# Sheet1.net
KiCad netlist of a schematic drawn in Altium Designer
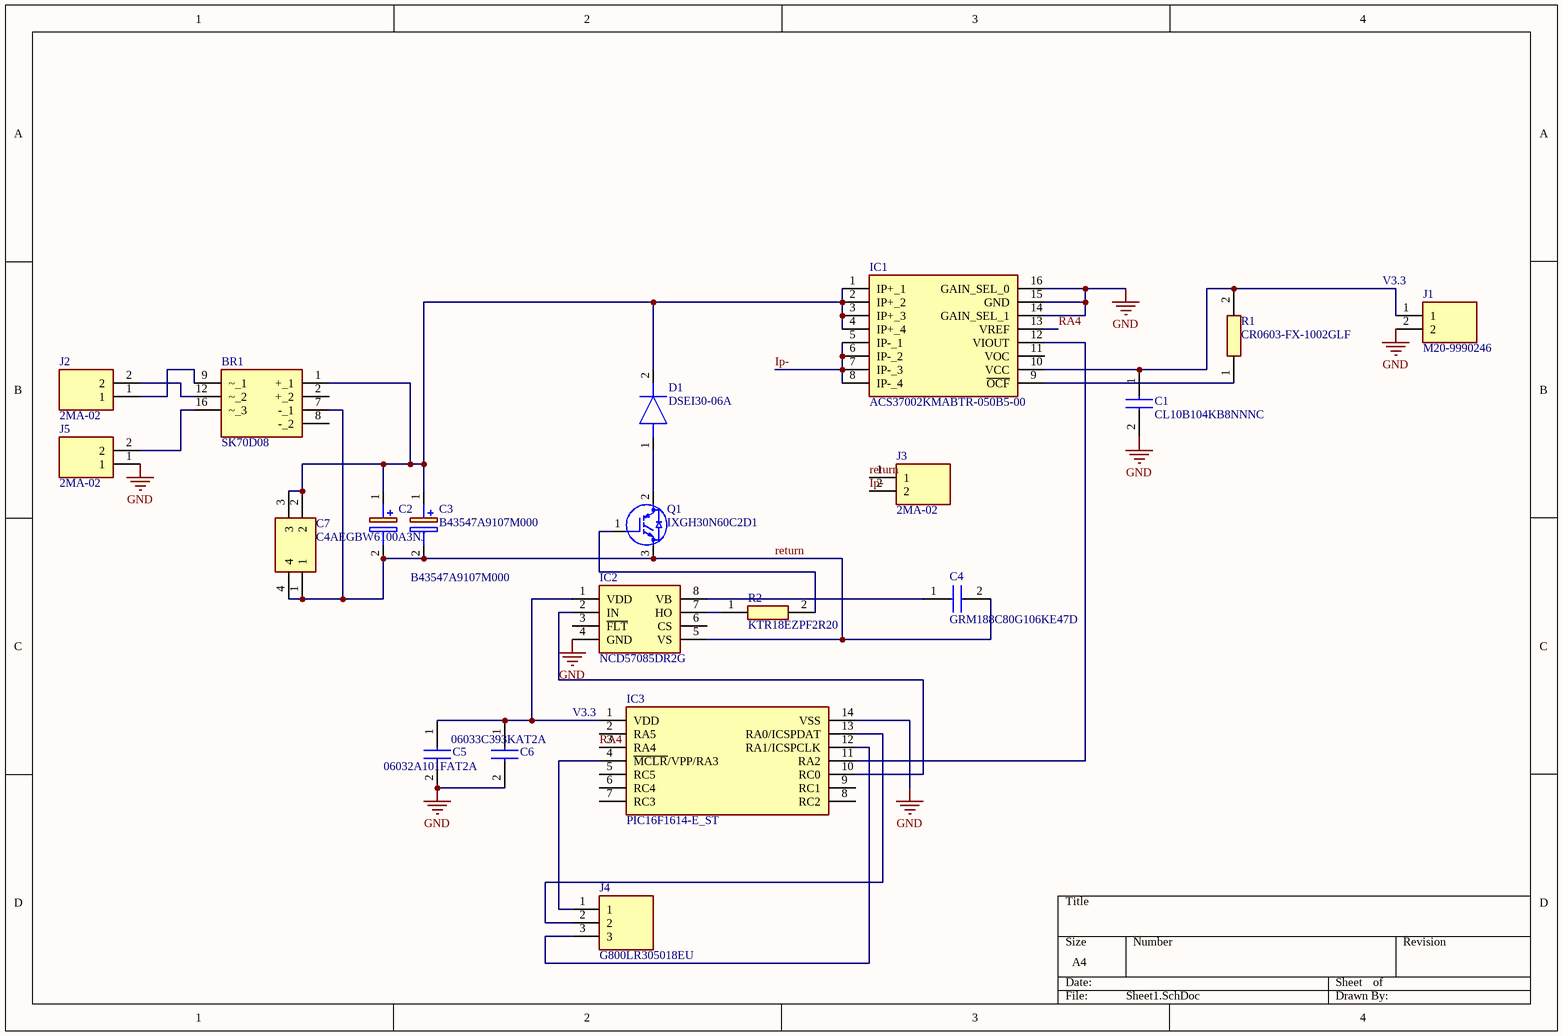
[diagram p0: Sheet1.SchDoc]

(export (version "E")
  (design (tool "Eeschema 10.0.6"))
  (components
    (comp (ref "BR1")
      (value "SK70D08")
      (footprint "SamacSys:SK70D08")
      (description "Bridge Rectifier")
      (libsource (lib "*") (part "SK70D08"))
    )
    (comp (ref "C1")
      (value "CL10B104KB8NNNC")
      (footprint "SamacSys:CAPC1608X90N")
      (description "Capacitor")
      (fields (field (name "MOUSER PART NUMBER") "187-CL10B104KB8NNNC"))
      (libsource (lib "*") (part "CL10B104KB8NNNC"))
    )
    (comp (ref "C2")
      (value "B43547A9107M000")
      (footprint "SamacSys:CAPPRD1000W190D2550H2700")
      (description "Capacitor Polarised")
      (fields (field (name "MOUSER PART NUMBER") "871-B43547A9107M000"))
      (libsource (lib "*") (part "B43547A9107M000"))
    )
    (comp (ref "C3")
      (value "B43547A9107M000")
      (footprint "SamacSys:CAPPRD1000W190D2550H2700")
      (description "Capacitor Polarised")
      (fields (field (name "MOUSER PART NUMBER") "871-B43547A9107M000"))
      (libsource (lib "*") (part "B43547A9107M000"))
    )
    (comp (ref "C4")
      (value "GRM188C80G106KE47D")
      (footprint "SamacSys:CAPC1608X90N")
      (description "Capacitor")
      (fields (field (name "MOUSER PART NUMBER") "81-GRM188C80G106KE7D"))
      (libsource (lib "*") (part "GRM188C80G106KE47D"))
    )
    (comp (ref "C5")
      (value "06032A101FAT2A")
      (footprint "SamacSys:CAPC1608X90N")
      (description "Capacitor")
      (fields (field (name "MOUSER PART NUMBER") "581-06032A101FAT2A"))
      (libsource (lib "*") (part "06032A101FAT2A"))
    )
    (comp (ref "C6")
      (value "06033C393KAT2A")
      (footprint "SamacSys:CAPC1608X90N")
      (description "Capacitor")
      (fields (field (name "MOUSER PART NUMBER") "581-06033C393K"))
      (libsource (lib "*") (part "06033C393KAT2A"))
    )
    (comp (ref "C7")
      (value "C4AEGBW6100A3NJ")
      (footprint "SamacSys:C4AEGBW6100A3NJ")
      (description "Capacitor")
      (libsource (lib "*") (part "C4AEGBW6100A3NJ"))
    )
    (comp (ref "D1")
      (value "DSEI30-06A")
      (footprint "SamacSys:TO1092P530X1586X2594-2P")
      (description "Diode")
      (fields (field (name "MOUSER PART NUMBER") "747-DSEI30-06A"))
      (libsource (lib "*") (part "DSEI30-06A"))
    )
    (comp (ref "IC1")
      (value "ACS37002KMABTR-050B5-00")
      (footprint "SamacSys:SOIC127P1030X265-16N")
      (description "Integrated Circuit")
      (libsource (lib "*") (part "ACS37002KMABTR-050B5-00"))
    )
    (comp (ref "IC2")
      (value "NCD57085DR2G")
      (footprint "SamacSys:SOIC127P600X175-8N")
      (description "Integrated Circuit")
      (fields (field (name "MOUSER PART NUMBER") "863-NCD57085DR2G"))
      (libsource (lib "*") (part "NCD57085DR2G"))
    )
    (comp (ref "IC3")
      (value "PIC16F1614-E_ST")
      (footprint "SamacSys:SOP65P640X120-14N")
      (description "Integrated Circuit")
      (fields
        (field (name "MANUFACTURER_PART_NUMBER") "PIC16F1614-E/ST")
        (field (name "MOUSER PART NUMBER") "579-PIC16F1614-E/ST")
      )
      (libsource (lib "*") (part "PIC16F1614-E_ST"))
    )
    (comp (ref "J1")
      (value "M20-9990246")
      (footprint "SamacSys:HDRV2W66P0X254_1X2_508X254X874P")
      (description "Connector")
      (fields (field (name "MOUSER PART NUMBER") "855-M20-9990246"))
      (libsource (lib "*") (part "M20-9990246"))
    )
    (comp (ref "J2")
      (value "2MA-02")
      (footprint "SamacSys:2MA02")
      (description "Connector")
      (fields (field (name "MOUSER PART NUMBER") "571-15460742"))
      (libsource (lib "*") (part "2MA-02"))
    )
    (comp (ref "J3")
      (value "2MA-02")
      (footprint "SamacSys:2MA02")
      (description "Connector")
      (fields (field (name "MOUSER PART NUMBER") "571-15460742"))
      (libsource (lib "") (part "2MA-02_1"))
    )
    (comp (ref "J4")
      (value "G800LR305018EU")
      (footprint "SamacSys:HDRV3W64P0X254_1X3_762X250X1082P")
      (description "Connector")
      (fields (field (name "MOUSER PART NUMBER") "523-G800LR305018EU"))
      (libsource (lib "*") (part "G800LR305018EU"))
    )
    (comp (ref "J5")
      (value "2MA-02")
      (footprint "SamacSys:2MA02")
      (description "Connector")
      (fields (field (name "MOUSER PART NUMBER") "571-15460742"))
      (libsource (lib "*") (part "2MA-02"))
    )
    (comp (ref "Q1")
      (value "IXGH30N60C2D1")
      (footprint "SamacSys:IXGH30N60C2D1")
      (description "Transistor IGBT")
      (libsource (lib "*") (part "IXGH30N60C2D1"))
    )
    (comp (ref "R1")
      (value "CR0603-FX-1002GLF")
      (footprint "SamacSys:RESC1608X55N")
      (description "Resistor")
      (fields (field (name "MOUSER PART NUMBER") "652-CR0603FX-1002GLF"))
      (libsource (lib "*") (part "CR0603-FX-1002GLF"))
    )
    (comp (ref "R2")
      (value "KTR18EZPF2R20")
      (footprint "SamacSys:RESC3216X65N")
      (description "Resistor")
      (fields (field (name "MOUSER PART NUMBER") "755-KTR18EZPF2R20"))
      (libsource (lib "*") (part "KTR18EZPF2R20"))
    )
  )
  (nets
    (net (code "1") (name "/Ip-") (class "Default")
      (node (ref "IC1") (pin "5") (pinfunction "IP-_1_5") (pintype "passive"))
      (node (ref "IC1") (pin "6") (pinfunction "IP-_2_6") (pintype "passive"))
      (node (ref "IC1") (pin "7") (pinfunction "IP-_3_7") (pintype "passive"))
      (node (ref "IC1") (pin "8") (pinfunction "IP-_4_8") (pintype "passive"))
      (node (ref "J3") (pin "2") (pinfunction "2_2") (pintype "passive"))
    )
    (net (code "2") (name "/RA4") (class "Default")
      (node (ref "IC1") (pin "13") (pinfunction "VREF_13") (pintype "passive"))
      (node (ref "IC3") (pin "3") (pinfunction "RA4_3") (pintype "passive"))
    )
    (net (code "3") (name "/return") (class "Default")
      (node (ref "BR1") (pin "7") (pinfunction "-_1_7") (pintype "passive"))
      (node (ref "C2") (pin "2") (pinfunction "-_2") (pintype "passive"))
      (node (ref "C3") (pin "2") (pinfunction "-_2") (pintype "passive"))
      (node (ref "C4") (pin "2") (pinfunction "2_2") (pintype "passive"))
      (node (ref "C7") (pin "1") (pinfunction "1_1") (pintype "passive"))
      (node (ref "C7") (pin "4") (pinfunction "4_4") (pintype "passive"))
      (node (ref "IC2") (pin "5") (pinfunction "VS_5") (pintype "passive"))
      (node (ref "J3") (pin "1") (pinfunction "1_1") (pintype "passive"))
      (node (ref "Q1") (pin "3") (pinfunction "E_3") (pintype "passive"))
    )
    (net (code "4") (name "GND") (class "Default")
      (node (ref "C1") (pin "2") (pinfunction "2_2") (pintype "passive"))
      (node (ref "C5") (pin "2") (pinfunction "2_2") (pintype "passive"))
      (node (ref "C6") (pin "2") (pinfunction "2_2") (pintype "passive"))
      (node (ref "IC1") (pin "14") (pinfunction "GAIN_SEL_1_14") (pintype "passive"))
      (node (ref "IC1") (pin "15") (pinfunction "GND_15") (pintype "passive"))
      (node (ref "IC1") (pin "16") (pinfunction "GAIN_SEL_0_16") (pintype "passive"))
      (node (ref "IC2") (pin "4") (pinfunction "GND_4") (pintype "passive"))
      (node (ref "IC3") (pin "14") (pinfunction "VSS_14") (pintype "passive"))
      (node (ref "J1") (pin "2") (pinfunction "2_2") (pintype "passive"))
      (node (ref "J5") (pin "1") (pinfunction "1_1") (pintype "passive"))
    )
    (net (code "5") (name "Net-(BR1-+_1)") (class "Default")
      (node (ref "BR1") (pin "1") (pinfunction "+_1_1") (pintype "passive"))
      (node (ref "C2") (pin "1") (pinfunction "+_1") (pintype "passive"))
      (node (ref "C3") (pin "1") (pinfunction "+_1") (pintype "passive"))
      (node (ref "C7") (pin "2") (pinfunction "2_2") (pintype "passive"))
      (node (ref "C7") (pin "3") (pinfunction "3_3") (pintype "passive"))
      (node (ref "D1") (pin "2") (pinfunction "K_2") (pintype "passive"))
      (node (ref "IC1") (pin "1") (pinfunction "IP+_1_1") (pintype "passive"))
      (node (ref "IC1") (pin "2") (pinfunction "IP+_2_2") (pintype "passive"))
      (node (ref "IC1") (pin "3") (pinfunction "IP+_3_3") (pintype "passive"))
      (node (ref "IC1") (pin "4") (pinfunction "IP+_4_4") (pintype "passive"))
    )
    (net (code "6") (name "Net-(BR1-~_1)") (class "Default")
      (node (ref "BR1") (pin "9") (pinfunction "~_1_9") (pintype "passive"))
      (node (ref "J2") (pin "1") (pinfunction "1_1") (pintype "passive"))
    )
    (net (code "7") (name "Net-(BR1-~_2)") (class "Default")
      (node (ref "BR1") (pin "12") (pinfunction "~_2_12") (pintype "passive"))
      (node (ref "J2") (pin "2") (pinfunction "2_2") (pintype "passive"))
    )
    (net (code "8") (name "Net-(BR1-~_3)") (class "Default")
      (node (ref "BR1") (pin "16") (pinfunction "~_3_16") (pintype "passive"))
      (node (ref "J5") (pin "2") (pinfunction "2_2") (pintype "passive"))
    )
    (net (code "9") (name "Net-(D1-A)") (class "Default")
      (node (ref "D1") (pin "1") (pinfunction "A_1") (pintype "passive"))
      (node (ref "Q1") (pin "2") (pinfunction "C_2") (pintype "passive"))
    )
    (net (code "10") (name "Net-(IC1-VCC)") (class "Default")
      (node (ref "C1") (pin "1") (pinfunction "1_1") (pintype "passive"))
      (node (ref "IC1") (pin "10") (pinfunction "VCC_10") (pintype "passive"))
      (node (ref "J1") (pin "1") (pinfunction "1_1") (pintype "passive"))
      (node (ref "R1") (pin "2") (pinfunction "2_2") (pintype "passive"))
    )
    (net (code "11") (name "Net-(IC1-VIOUT)") (class "Default")
      (node (ref "IC1") (pin "12") (pinfunction "VIOUT_12") (pintype "passive"))
      (node (ref "IC3") (pin "11") (pinfunction "RA2_11") (pintype "passive"))
    )
    (net (code "12") (name "Net-(IC1-~{OCF})") (class "Default")
      (node (ref "IC1") (pin "9") (pinfunction "~{OCF}_9") (pintype "passive"))
      (node (ref "R1") (pin "1") (pinfunction "1_1") (pintype "passive"))
    )
    (net (code "13") (name "Net-(IC2-HO)") (class "Default")
      (node (ref "IC2") (pin "7") (pinfunction "HO_7") (pintype "passive"))
      (node (ref "R2") (pin "1") (pinfunction "1_1") (pintype "passive"))
    )
    (net (code "14") (name "Net-(IC2-IN)") (class "Default")
      (node (ref "IC2") (pin "2") (pinfunction "IN_2") (pintype "passive"))
      (node (ref "IC3") (pin "10") (pinfunction "RC0_10") (pintype "passive"))
    )
    (net (code "15") (name "Net-(IC2-VB)") (class "Default")
      (node (ref "C4") (pin "1") (pinfunction "1_1") (pintype "passive"))
      (node (ref "IC2") (pin "8") (pinfunction "VB_8") (pintype "passive"))
    )
    (net (code "16") (name "Net-(IC2-VDD)") (class "Default")
      (node (ref "C5") (pin "1") (pinfunction "1_1") (pintype "passive"))
      (node (ref "C6") (pin "1") (pinfunction "1_1") (pintype "passive"))
      (node (ref "IC2") (pin "1") (pinfunction "VDD_1") (pintype "passive"))
      (node (ref "IC3") (pin "1") (pinfunction "VDD_1") (pintype "passive"))
    )
    (net (code "17") (name "Net-(IC3-RA0{slash}ICSPDAT)") (class "Default")
      (node (ref "IC3") (pin "13") (pinfunction "RA0/ICSPDAT_13") (pintype "passive"))
      (node (ref "J4") (pin "2") (pinfunction "2_2") (pintype "passive"))
    )
    (net (code "18") (name "Net-(IC3-RA1{slash}ICSPCLK)") (class "Default")
      (node (ref "IC3") (pin "12") (pinfunction "RA1/ICSPCLK_12") (pintype "passive"))
      (node (ref "J4") (pin "3") (pinfunction "3_3") (pintype "passive"))
    )
    (net (code "19") (name "Net-(IC3-~{MCLR}{slash}VPP{slash}RA3)") (class "Default")
      (node (ref "IC3") (pin "4") (pinfunction "~{MCLR}/VPP/RA3_4") (pintype "passive"))
      (node (ref "J4") (pin "1") (pinfunction "1_1") (pintype "passive"))
    )
    (net (code "20") (name "Net-(Q1-G)") (class "Default")
      (node (ref "Q1") (pin "1") (pinfunction "G_1") (pintype "passive"))
      (node (ref "R2") (pin "2") (pinfunction "2_2") (pintype "passive"))
    )
    (net (code "21") (name "unconnected-(BR1-+_2-Pad2)") (class "Default")
      (node (ref "BR1") (pin "2") (pinfunction "+_2_2") (pintype "passive"))
    )
    (net (code "22") (name "unconnected-(BR1--_2-Pad8)") (class "Default")
      (node (ref "BR1") (pin "8") (pinfunction "-_2_8") (pintype "passive"))
    )
    (net (code "23") (name "unconnected-(IC1-VOC-Pad11)") (class "Default")
      (node (ref "IC1") (pin "11") (pinfunction "VOC_11") (pintype "passive"))
    )
    (net (code "24") (name "unconnected-(IC2-CS-Pad6)") (class "Default")
      (node (ref "IC2") (pin "6") (pinfunction "CS_6") (pintype "passive"))
    )
    (net (code "25") (name "unconnected-(IC2-~{FLT}-Pad3)") (class "Default")
      (node (ref "IC2") (pin "3") (pinfunction "~{FLT}_3") (pintype "passive"))
    )
    (net (code "26") (name "unconnected-(IC3-RA5-Pad2)") (class "Default")
      (node (ref "IC3") (pin "2") (pinfunction "RA5_2") (pintype "passive"))
    )
    (net (code "27") (name "unconnected-(IC3-RC1-Pad9)") (class "Default")
      (node (ref "IC3") (pin "9") (pinfunction "RC1_9") (pintype "passive"))
    )
    (net (code "28") (name "unconnected-(IC3-RC2-Pad8)") (class "Default")
      (node (ref "IC3") (pin "8") (pinfunction "RC2_8") (pintype "passive"))
    )
    (net (code "29") (name "unconnected-(IC3-RC3-Pad7)") (class "Default")
      (node (ref "IC3") (pin "7") (pinfunction "RC3_7") (pintype "passive"))
    )
    (net (code "30") (name "unconnected-(IC3-RC4-Pad6)") (class "Default")
      (node (ref "IC3") (pin "6") (pinfunction "RC4_6") (pintype "passive"))
    )
    (net (code "31") (name "unconnected-(IC3-RC5-Pad5)") (class "Default")
      (node (ref "IC3") (pin "5") (pinfunction "RC5_5") (pintype "passive"))
    )
  )
)
